# LoraEp.net
KiCad netlist of a schematic drawn in Altium Designer
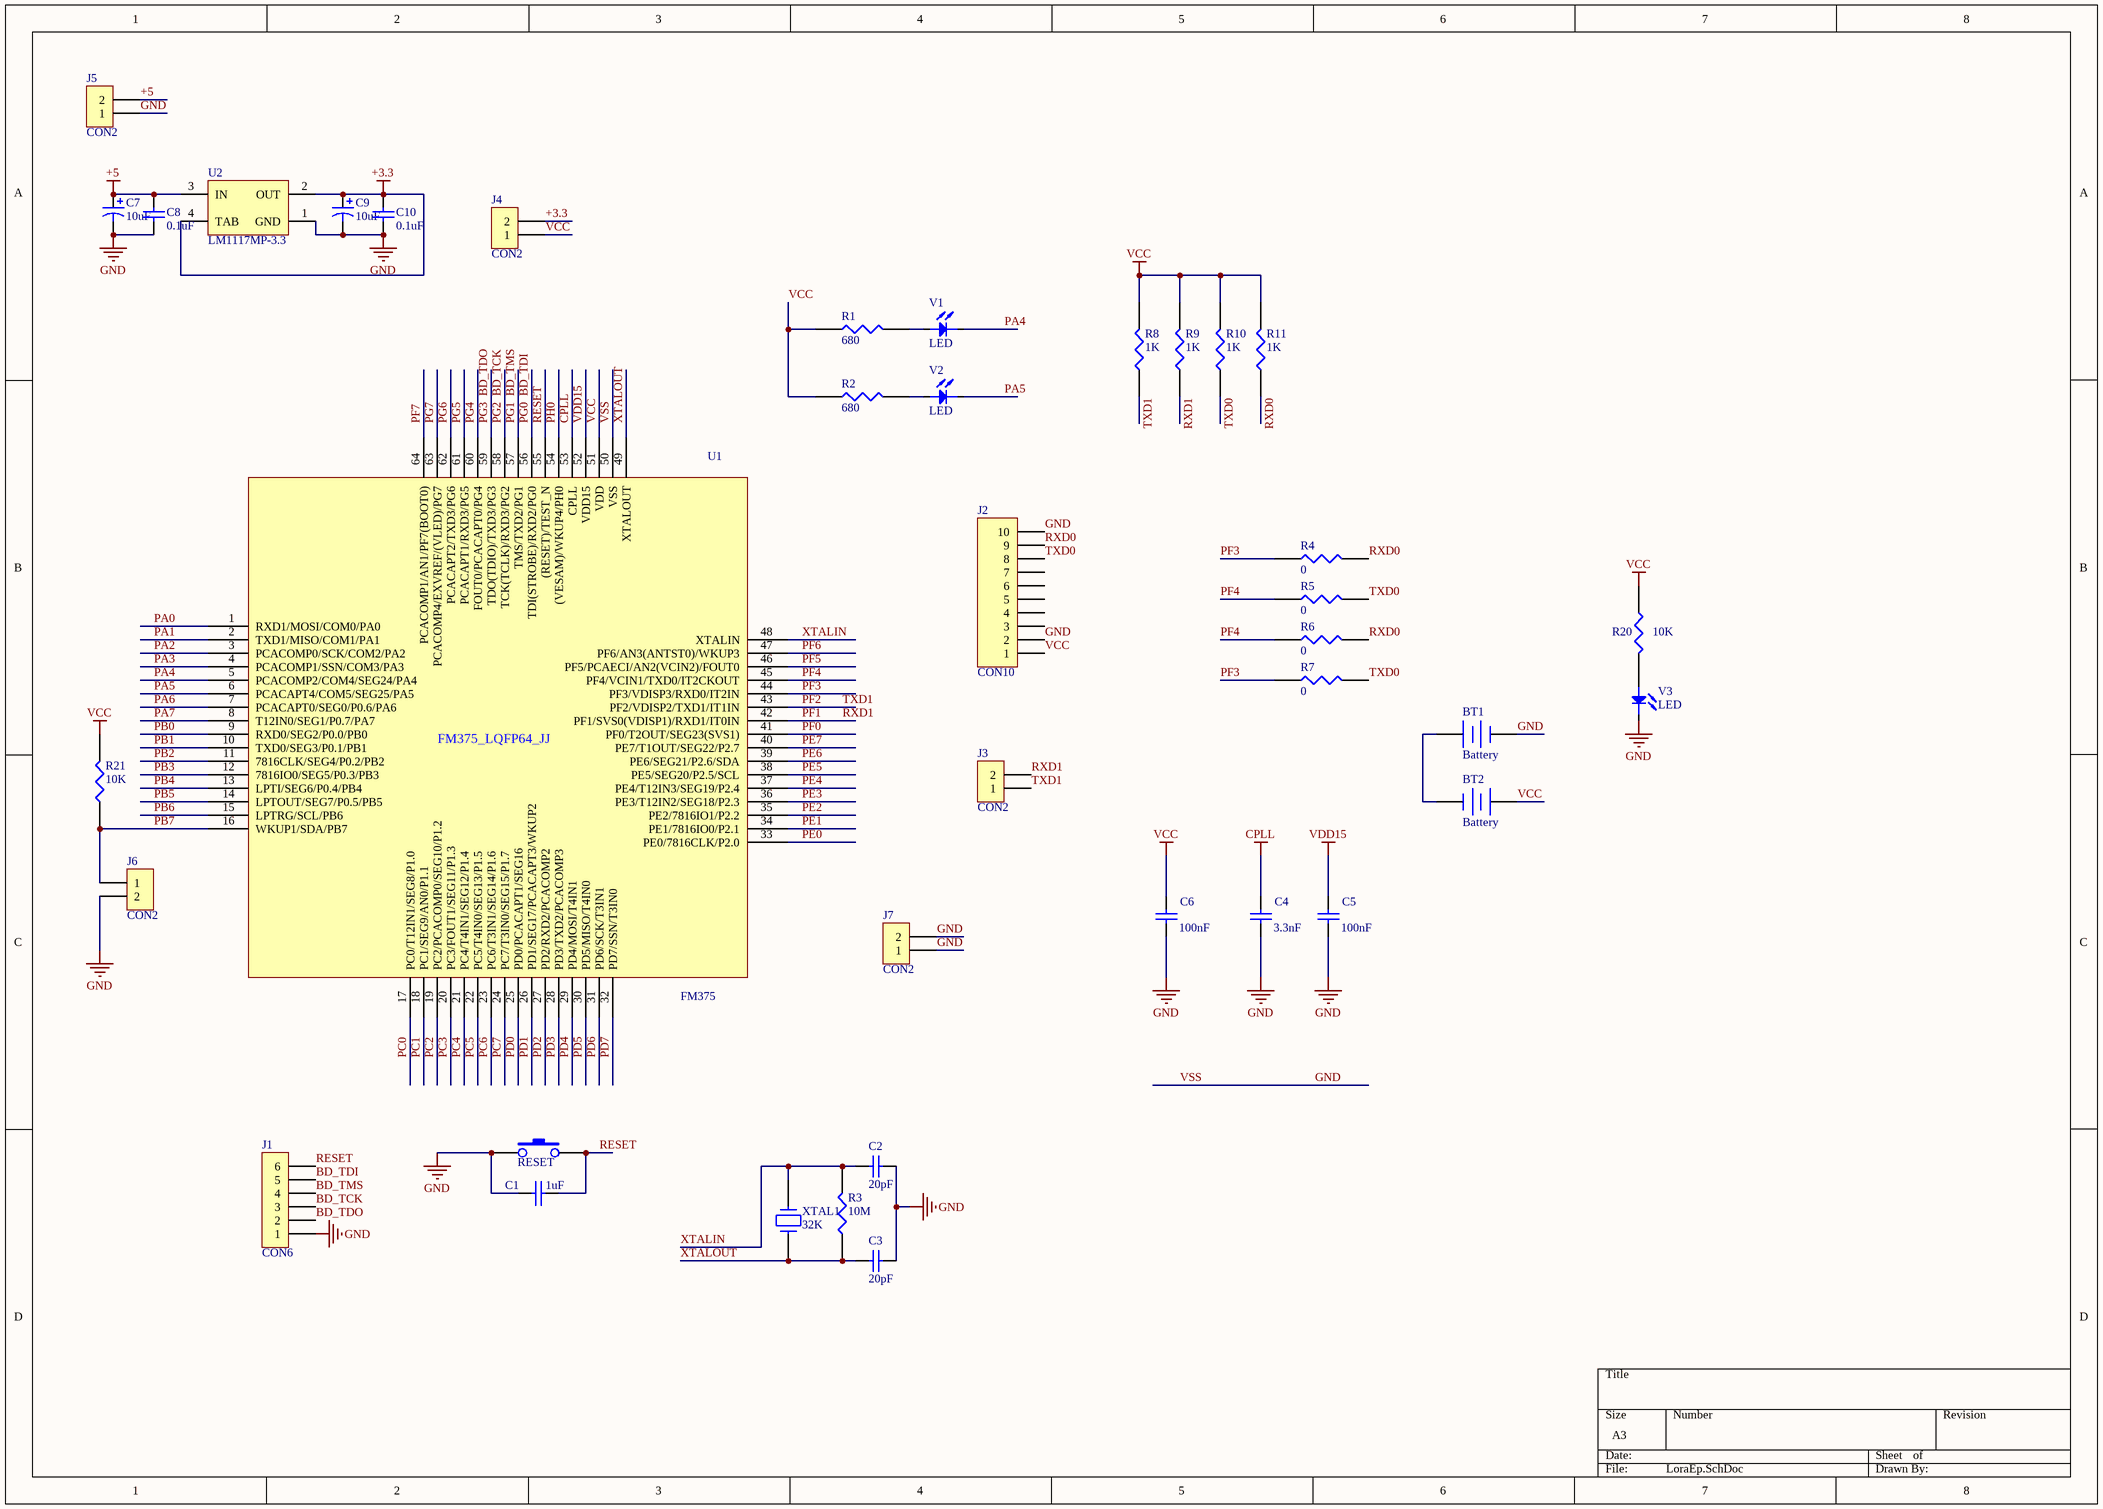
[diagram p0: LoraEp.SchDoc]

(export (version "E")
  (design (tool "Eeschema 10.0.6"))
  (components
    (comp (ref "BT1")
      (value "Battery")
      (footprint "BAT")
      (description "Multicell Battery")
      (fields (field (name "PUBLISHER") "Altium Limited"))
      (libsource (lib "Miscellaneous Devices") (part "Battery"))
    )
    (comp (ref "BT2")
      (value "Battery")
      (footprint "BAT")
      (description "Multicell Battery")
      (fields (field (name "PUBLISHER") "Altium Limited"))
      (libsource (lib "Miscellaneous Devices") (part "Battery"))
    )
    (comp (ref "C1")
      (value "1uF")
      (footprint "0805")
      (description "一般瓷片电容、直插选用RAD0.1，贴片选用0805")
      (libsource (lib "FM_SCH") (part "CAP"))
    )
    (comp (ref "C2")
      (value "20pF")
      (footprint "0805")
      (description "Capacitor")
      (fields (field (name "PUBLISHER") "Altium Limited"))
      (libsource (lib "Miscellaneous Devices") (part "Cap"))
    )
    (comp (ref "C3")
      (value "20pF")
      (footprint "0805")
      (description "Capacitor")
      (fields (field (name "PUBLISHER") "Altium Limited"))
      (libsource (lib "Miscellaneous Devices") (part "Cap"))
    )
    (comp (ref "C4")
      (value "3.3nF")
      (footprint "0805")
      (description "Capacitor")
      (fields (field (name "PUBLISHER") "Altium Limited"))
      (libsource (lib "Miscellaneous Devices") (part "Cap"))
    )
    (comp (ref "C5")
      (value "100nF")
      (footprint "0805")
      (description "Capacitor")
      (fields (field (name "PUBLISHER") "Altium Limited"))
      (libsource (lib "Miscellaneous Devices") (part "Cap"))
    )
    (comp (ref "C6")
      (value "100nF")
      (footprint "0805")
      (description "Capacitor")
      (fields (field (name "PUBLISHER") "Altium Limited"))
      (libsource (lib "Miscellaneous Devices") (part "Cap"))
    )
    (comp (ref "C7")
      (value "10uF")
      (footprint "0805")
      (description "Polarized Capacitor (Radial)")
      (fields (field (name "PUBLISHER") "Altium Limited"))
      (libsource (lib "Miscellaneous Devices") (part "Cap Pol1"))
    )
    (comp (ref "C8")
      (value "0.1uF")
      (footprint "0805")
      (description "Capacitor")
      (fields (field (name "PUBLISHER") "Altium Limited"))
      (libsource (lib "Miscellaneous Devices") (part "Cap"))
    )
    (comp (ref "C9")
      (value "10uF")
      (footprint "0805")
      (description "Polarized Capacitor (Radial)")
      (fields (field (name "PUBLISHER") "Altium Limited"))
      (libsource (lib "Miscellaneous Devices") (part "Cap Pol1"))
    )
    (comp (ref "C10")
      (value "0.1uF")
      (footprint "0805")
      (description "Capacitor")
      (fields (field (name "PUBLISHER") "Altium Limited"))
      (libsource (lib "Miscellaneous Devices") (part "Cap"))
    )
    (comp (ref "J1")
      (value "CON6")
      (footprint "SIP6")
      (description "Connector")
      (libsource (lib "YPF") (part "CON6"))
    )
    (comp (ref "J2")
      (value "CON10")
      (footprint "SSIP10")
      (description "Connector")
      (libsource (lib "YPF") (part "CON10"))
    )
    (comp (ref "J3")
      (value "CON2")
      (footprint "SIP2")
      (description "Connector")
      (libsource (lib "YPF") (part "CON2"))
    )
    (comp (ref "J4")
      (value "CON2")
      (footprint "SIP2")
      (description "Connector")
      (libsource (lib "YPF") (part "CON2"))
    )
    (comp (ref "J5")
      (value "CON2")
      (footprint "SourPad")
      (description "Connector")
      (libsource (lib "YPF") (part "CON2"))
    )
    (comp (ref "J6")
      (value "CON2")
      (footprint "SIP2")
      (description "Connector")
      (libsource (lib "") (part "CON2_1"))
    )
    (comp (ref "J7")
      (value "CON2")
      (footprint "HDR1X2")
      (description "Connector")
      (libsource (lib "YPF") (part "CON2"))
    )
    (comp (ref "R1")
      (value "680")
      (footprint "0805")
      (description "电阻，1/4w的金属膜直插可选AXIAL0.4封装（长度10mm），贴片可选0805封装，其他电阻可选AXIAL0.5～AXIAL1.0")
      (libsource (lib "*") (part "RES1"))
    )
    (comp (ref "R2")
      (value "680")
      (footprint "0805")
      (description "电阻，1/4w的金属膜直插可选AXIAL0.4封装（长度10mm），贴片可选0805封装，其他电阻可选AXIAL0.5～AXIAL1.0")
      (libsource (lib "*") (part "RES1"))
    )
    (comp (ref "R3") (value "10M") (footprint "0805") (libsource (lib "FM301_TEST") (part "RES1")))
    (comp (ref "R4")
      (value "0")
      (footprint "0805")
      (description "电阻，1/4w的金属膜直插可选AXIAL0.4封装（长度10mm），贴片可选0805封装，其他电阻可选AXIAL0.5～AXIAL1.0")
      (libsource (lib "*") (part "RES1"))
    )
    (comp (ref "R5")
      (value "0")
      (footprint "0805")
      (description "电阻，1/4w的金属膜直插可选AXIAL0.4封装（长度10mm），贴片可选0805封装，其他电阻可选AXIAL0.5～AXIAL1.0")
      (libsource (lib "*") (part "RES1"))
    )
    (comp (ref "R6")
      (value "0")
      (footprint "0805")
      (description "电阻，1/4w的金属膜直插可选AXIAL0.4封装（长度10mm），贴片可选0805封装，其他电阻可选AXIAL0.5～AXIAL1.0")
      (libsource (lib "*") (part "RES1"))
    )
    (comp (ref "R7")
      (value "0")
      (footprint "0805")
      (description "电阻，1/4w的金属膜直插可选AXIAL0.4封装（长度10mm），贴片可选0805封装，其他电阻可选AXIAL0.5～AXIAL1.0")
      (libsource (lib "*") (part "RES1"))
    )
    (comp (ref "R8")
      (value "1K")
      (footprint "0805")
      (description "电阻，1/4w的金属膜直插可选AXIAL0.4封装（长度10mm），贴片可选0805封装，其他电阻可选AXIAL0.5～AXIAL1.0")
      (libsource (lib "*") (part "RES1"))
    )
    (comp (ref "R9")
      (value "1K")
      (footprint "0805")
      (description "电阻，1/4w的金属膜直插可选AXIAL0.4封装（长度10mm），贴片可选0805封装，其他电阻可选AXIAL0.5～AXIAL1.0")
      (libsource (lib "*") (part "RES1"))
    )
    (comp (ref "R10")
      (value "1K")
      (footprint "0805")
      (description "电阻，1/4w的金属膜直插可选AXIAL0.4封装（长度10mm），贴片可选0805封装，其他电阻可选AXIAL0.5～AXIAL1.0")
      (libsource (lib "*") (part "RES1"))
    )
    (comp (ref "R11")
      (value "1K")
      (footprint "0805")
      (description "电阻，1/4w的金属膜直插可选AXIAL0.4封装（长度10mm），贴片可选0805封装，其他电阻可选AXIAL0.5～AXIAL1.0")
      (libsource (lib "*") (part "RES1"))
    )
    (comp (ref "R20")
      (value "10K")
      (footprint "0805")
      (description "电阻，1/4w的金属膜直插可选AXIAL0.4封装（长度10mm），贴片可选0805封装，其他电阻可选AXIAL0.5～AXIAL1.0")
      (libsource (lib "*") (part "RES1"))
    )
    (comp (ref "R21")
      (value "10K")
      (footprint "0805")
      (description "电阻，1/4w的金属膜直插可选AXIAL0.4封装（长度10mm），贴片可选0805封装，其他电阻可选AXIAL0.5～AXIAL1.0")
      (libsource (lib "*") (part "RES1"))
    )
    (comp (ref "RESET")
      (value "KEY")
      (footprint "YPF:BUTTON-S")
      (description "乒乓球按键（压下后接通，松开自动断开），较大按键尺寸12mmX12mm选用BUTTON-L封装，较小尺寸6mmX6mm选用BUTTON-S封装")
      (libsource (lib "*") (part "SW-PB"))
    )
    (comp (ref "U1")
      (value "FM375")
      (footprint "LQFP64-0.5")
      (libsource (lib "FM375_LQFP64_SOCKET") (part "LQFP64-JJ"))
    )
    (comp (ref "U2")
      (value "LM1117MP-3.3")
      (footprint "MP04A_L")
      (description "800mA Low-Dropout Linear Regulator")
      (fields
        (field (name "MANUFACTURER") "National Semiconductor")
        (field (name "DIGIKEYPARTNUMBER") "LM1117MP-3.3CT-ND")
        (field (name "PUBLISHER") "Altium Limited")
      )
      (libsource (lib "NSC LDO") (part "LM1117MP-3.3"))
    )
    (comp (ref "V1") (value "LED") (footprint "SIP2") (libsource (lib "YPF") (part "LED")))
    (comp (ref "V2") (value "LED") (footprint "SIP2") (libsource (lib "YPF") (part "LED")))
    (comp (ref "V3") (value "LED") (footprint "0805") (libsource (lib "YPF") (part "LED")))
    (comp (ref "XTAL1")
      (value "32K")
      (footprint "XTAL-RB32K_2")
      (description "Crystal")
      (libsource (lib "FM301_TEST") (part "CRYSTAL"))
    )
  )
  (nets
    (net (code "1") (name "+3.3") (class "Default")
      (node (ref "C10") (pin "2") (pinfunction "2_2") (pintype "passive"))
      (node (ref "C9") (pin "1") (pinfunction "1_1") (pintype "passive"))
      (node (ref "J4") (pin "2") (pinfunction "2_2") (pintype "passive"))
      (node (ref "U2") (pin "2") (pinfunction "OUT_2") (pintype "power_in"))
      (node (ref "U2") (pin "4") (pinfunction "TAB_4") (pintype "power_in"))
    )
    (net (code "2") (name "+5") (class "Default")
      (node (ref "C7") (pin "1") (pinfunction "1_1") (pintype "passive"))
      (node (ref "C8") (pin "2") (pinfunction "2_2") (pintype "passive"))
      (node (ref "J5") (pin "2") (pinfunction "2_2") (pintype "passive"))
      (node (ref "U2") (pin "3") (pinfunction "IN_3") (pintype "power_in"))
    )
    (net (code "3") (name "/BD_TCK") (class "Default")
      (node (ref "J1") (pin "3") (pinfunction "3_3") (pintype "passive"))
      (node (ref "U1") (pin "58") (pinfunction "TCK(TCLK)/RXD3/PG2_58") (pintype "passive"))
    )
    (net (code "4") (name "/BD_TDI") (class "Default")
      (node (ref "J1") (pin "5") (pinfunction "5_5") (pintype "passive"))
      (node (ref "U1") (pin "56") (pinfunction "TDI(STROBE)/RXD2/PG0_56") (pintype "passive"))
    )
    (net (code "5") (name "/BD_TDO") (class "Default")
      (node (ref "J1") (pin "2") (pinfunction "2_2") (pintype "passive"))
      (node (ref "U1") (pin "59") (pinfunction "TDO(TDIO)/TXD3/PG3_59") (pintype "passive"))
    )
    (net (code "6") (name "/BD_TMS") (class "Default")
      (node (ref "J1") (pin "4") (pinfunction "4_4") (pintype "passive"))
      (node (ref "U1") (pin "57") (pinfunction "TMS/TXD2/PG1_57") (pintype "passive"))
    )
    (net (code "7") (name "/PA0") (class "Default")
      (node (ref "U1") (pin "1") (pinfunction "RXD1/MOSI/COM0/PA0_1") (pintype "passive"))
    )
    (net (code "8") (name "/PA1") (class "Default")
      (node (ref "U1") (pin "2") (pinfunction "TXD1/MISO/COM1/PA1_2") (pintype "passive"))
    )
    (net (code "9") (name "/PA2") (class "Default")
      (node (ref "U1") (pin "3") (pinfunction "PCACOMP0/SCK/COM2/PA2_3") (pintype "passive"))
    )
    (net (code "10") (name "/PA3") (class "Default")
      (node (ref "U1") (pin "4") (pinfunction "PCACOMP1/SSN/COM3/PA3_4") (pintype "passive"))
    )
    (net (code "11") (name "/PA4") (class "Default")
      (node (ref "U1") (pin "5") (pinfunction "PCACOMP2/COM4/SEG24/PA4_5") (pintype "passive"))
      (node (ref "V1") (pin "2") (pintype "passive"))
    )
    (net (code "12") (name "/PA5") (class "Default")
      (node (ref "U1") (pin "6") (pinfunction "PCACAPT4/COM5/SEG25/PA5_6") (pintype "passive"))
      (node (ref "V2") (pin "2") (pintype "passive"))
    )
    (net (code "13") (name "/PA6") (class "Default")
      (node (ref "U1") (pin "7") (pinfunction "PCACAPT0/SEG0/P0.6/PA6_7") (pintype "passive"))
    )
    (net (code "14") (name "/PA7") (class "Default")
      (node (ref "U1") (pin "8") (pinfunction "T12IN0/SEG1/P0.7/PA7_8") (pintype "passive"))
    )
    (net (code "15") (name "/PB0") (class "Default")
      (node (ref "U1") (pin "9") (pinfunction "RXD0/SEG2/P0.0/PB0_9") (pintype "passive"))
    )
    (net (code "16") (name "/PB1") (class "Default")
      (node (ref "U1") (pin "10") (pinfunction "TXD0/SEG3/P0.1/PB1_10") (pintype "passive"))
    )
    (net (code "17") (name "/PB2") (class "Default")
      (node (ref "U1") (pin "11") (pinfunction "7816CLK/SEG4/P0.2/PB2_11") (pintype "passive"))
    )
    (net (code "18") (name "/PB3") (class "Default")
      (node (ref "U1") (pin "12") (pinfunction "7816IO0/SEG5/P0.3/PB3_12") (pintype "passive"))
    )
    (net (code "19") (name "/PB4") (class "Default")
      (node (ref "U1") (pin "13") (pinfunction "LPTI/SEG6/P0.4/PB4_13") (pintype "passive"))
    )
    (net (code "20") (name "/PB5") (class "Default")
      (node (ref "U1") (pin "14") (pinfunction "LPTOUT/SEG7/P0.5/PB5_14") (pintype "passive"))
    )
    (net (code "21") (name "/PB6") (class "Default")
      (node (ref "U1") (pin "15") (pinfunction "LPTRG/SCL/PB6_15") (pintype "passive"))
    )
    (net (code "22") (name "/PB7") (class "Default")
      (node (ref "J6") (pin "1") (pinfunction "1_1") (pintype "passive"))
      (node (ref "R21") (pin "1") (pinfunction "1_1") (pintype "passive"))
      (node (ref "U1") (pin "16") (pinfunction "WKUP1/SDA/PB7_16") (pintype "passive"))
    )
    (net (code "23") (name "/PC0") (class "Default")
      (node (ref "U1") (pin "17") (pinfunction "PC0/T12IN1/SEG8/P1.0_17") (pintype "passive"))
    )
    (net (code "24") (name "/PC1") (class "Default")
      (node (ref "U1") (pin "18") (pinfunction "PC1/SEG9/AN0/P1.1_18") (pintype "passive"))
    )
    (net (code "25") (name "/PC2") (class "Default")
      (node (ref "U1") (pin "19") (pinfunction "PC2/PCACOMP0/SEG10/P1.2_19") (pintype "passive"))
    )
    (net (code "26") (name "/PC3") (class "Default")
      (node (ref "U1") (pin "20") (pinfunction "PC3/FOUT1/SEG11/P1.3_20") (pintype "passive"))
    )
    (net (code "27") (name "/PC4") (class "Default")
      (node (ref "U1") (pin "21") (pinfunction "PC4/T4IN1/SEG12/P1.4_21") (pintype "passive"))
    )
    (net (code "28") (name "/PC5") (class "Default")
      (node (ref "U1") (pin "22") (pinfunction "PC5/T4IN0/SEG13/P1.5_22") (pintype "passive"))
    )
    (net (code "29") (name "/PC6") (class "Default")
      (node (ref "U1") (pin "23") (pinfunction "PC6/T3IN1/SEG14/P1.6_23") (pintype "passive"))
    )
    (net (code "30") (name "/PC7") (class "Default")
      (node (ref "U1") (pin "24") (pinfunction "PC7/T3IN0/SEG15/P1.7_24") (pintype "passive"))
    )
    (net (code "31") (name "/PD0") (class "Default")
      (node (ref "U1") (pin "25") (pinfunction "PD0/PCACAPT1/SEG16_25") (pintype "passive"))
    )
    (net (code "32") (name "/PD1") (class "Default")
      (node (ref "U1") (pin "26") (pinfunction "PD1/SEG17/PCACAPT3/WKUP2_26") (pintype "passive"))
    )
    (net (code "33") (name "/PD2") (class "Default")
      (node (ref "U1") (pin "27") (pinfunction "PD2/RXD2/PCACOMP2_27") (pintype "passive"))
    )
    (net (code "34") (name "/PD3") (class "Default")
      (node (ref "U1") (pin "28") (pinfunction "PD3/TXD2/PCACOMP3_28") (pintype "passive"))
    )
    (net (code "35") (name "/PD4") (class "Default")
      (node (ref "U1") (pin "29") (pinfunction "PD4/MOSI/T4IN1_29") (pintype "passive"))
    )
    (net (code "36") (name "/PD5") (class "Default")
      (node (ref "U1") (pin "30") (pinfunction "PD5/MISO/T4IN0_30") (pintype "passive"))
    )
    (net (code "37") (name "/PD6") (class "Default")
      (node (ref "U1") (pin "31") (pinfunction "PD6/SCK/T3IN1_31") (pintype "passive"))
    )
    (net (code "38") (name "/PD7") (class "Default")
      (node (ref "U1") (pin "32") (pinfunction "PD7/SSN/T3IN0_32") (pintype "passive"))
    )
    (net (code "39") (name "/PE0") (class "Default")
      (node (ref "U1") (pin "33") (pinfunction "PE0/7816CLK/P2.0_33") (pintype "passive"))
    )
    (net (code "40") (name "/PE1") (class "Default")
      (node (ref "U1") (pin "34") (pinfunction "PE1/7816IO0/P2.1_34") (pintype "passive"))
    )
    (net (code "41") (name "/PE2") (class "Default")
      (node (ref "U1") (pin "35") (pinfunction "PE2/7816IO1/P2.2_35") (pintype "passive"))
    )
    (net (code "42") (name "/PE3") (class "Default")
      (node (ref "U1") (pin "36") (pinfunction "PE3/T12IN2/SEG18/P2.3_36") (pintype "passive"))
    )
    (net (code "43") (name "/PE4") (class "Default")
      (node (ref "U1") (pin "37") (pinfunction "PE4/T12IN3/SEG19/P2.4_37") (pintype "passive"))
    )
    (net (code "44") (name "/PE5") (class "Default")
      (node (ref "U1") (pin "38") (pinfunction "PE5/SEG20/P2.5/SCL_38") (pintype "passive"))
    )
    (net (code "45") (name "/PE6") (class "Default")
      (node (ref "U1") (pin "39") (pinfunction "PE6/SEG21/P2.6/SDA_39") (pintype "passive"))
    )
    (net (code "46") (name "/PE7") (class "Default")
      (node (ref "U1") (pin "40") (pinfunction "PE7/T1OUT/SEG22/P2.7_40") (pintype "passive"))
    )
    (net (code "47") (name "/PF0") (class "Default")
      (node (ref "U1") (pin "41") (pinfunction "PF0/T2OUT/SEG23(SVS1)_41") (pintype "passive"))
    )
    (net (code "48") (name "/PF1") (class "Default")
      (node (ref "J3") (pin "2") (pinfunction "2_2") (pintype "passive"))
      (node (ref "R9") (pin "1") (pinfunction "1_1") (pintype "passive"))
      (node (ref "U1") (pin "42") (pinfunction "PF1/SVS0(VDISP1)/RXD1/IT0IN_42") (pintype "passive"))
    )
    (net (code "49") (name "/PF2") (class "Default")
      (node (ref "J3") (pin "1") (pinfunction "1_1") (pintype "passive"))
      (node (ref "R8") (pin "1") (pinfunction "1_1") (pintype "passive"))
      (node (ref "U1") (pin "43") (pinfunction "PF2/VDISP2/TXD1/IT1IN_43") (pintype "passive"))
    )
    (net (code "50") (name "/PF3") (class "Default")
      (node (ref "R4") (pin "1") (pinfunction "1_1") (pintype "passive"))
      (node (ref "R7") (pin "1") (pinfunction "1_1") (pintype "passive"))
      (node (ref "U1") (pin "44") (pinfunction "PF3/VDISP3/RXD0/IT2IN_44") (pintype "passive"))
    )
    (net (code "51") (name "/PF4") (class "Default")
      (node (ref "R5") (pin "1") (pinfunction "1_1") (pintype "passive"))
      (node (ref "R6") (pin "1") (pinfunction "1_1") (pintype "passive"))
      (node (ref "U1") (pin "45") (pinfunction "PF4/VCIN1/TXD0/IT2CKOUT_45") (pintype "passive"))
    )
    (net (code "52") (name "/PF5") (class "Default")
      (node (ref "U1") (pin "46") (pinfunction "PF5/PCAECI/AN2(VCIN2)/FOUT0_46") (pintype "passive"))
    )
    (net (code "53") (name "/PF6") (class "Default")
      (node (ref "U1") (pin "47") (pinfunction "PF6/AN3(ANTST0)/WKUP3_47") (pintype "passive"))
    )
    (net (code "54") (name "/PF7") (class "Default")
      (node (ref "U1") (pin "64") (pinfunction "PCACOMP1/AN1/PF7(BOOT0)_64") (pintype "passive"))
    )
    (net (code "55") (name "/PG4") (class "Default")
      (node (ref "U1") (pin "60") (pinfunction "FOUT0/PCACAPT0/PG4_60") (pintype "passive"))
    )
    (net (code "56") (name "/PG5") (class "Default")
      (node (ref "U1") (pin "61") (pinfunction "PCACAPT1/RXD3/PG5_61") (pintype "passive"))
    )
    (net (code "57") (name "/PG6") (class "Default")
      (node (ref "U1") (pin "62") (pinfunction "PCACAPT2/TXD3/PG6_62") (pintype "passive"))
    )
    (net (code "58") (name "/PG7") (class "Default")
      (node (ref "U1") (pin "63") (pinfunction "PCACOMP4/EXVREF/(VLED)/PG7_63") (pintype "passive"))
    )
    (net (code "59") (name "/PH0") (class "Default")
      (node (ref "U1") (pin "54") (pinfunction "(VESAM)/WKUP4/PH0_54") (pintype "passive"))
    )
    (net (code "60") (name "/RESET") (class "Default")
      (node (ref "C1") (pin "1") (pinfunction "1_1") (pintype "passive"))
      (node (ref "J1") (pin "6") (pinfunction "6_6") (pintype "passive"))
      (node (ref "RESET") (pin "2") (pinfunction "2_2") (pintype "passive"))
      (node (ref "U1") (pin "55") (pinfunction "(RESET)/TEST_N_55") (pintype "passive"))
    )
    (net (code "61") (name "/RXD0") (class "Default")
      (node (ref "J2") (pin "9") (pinfunction "9_9") (pintype "passive"))
      (node (ref "R11") (pin "1") (pinfunction "1_1") (pintype "passive"))
      (node (ref "R4") (pin "2") (pinfunction "2_2") (pintype "passive"))
      (node (ref "R6") (pin "2") (pinfunction "2_2") (pintype "passive"))
    )
    (net (code "62") (name "/TXD0") (class "Default")
      (node (ref "J2") (pin "8") (pinfunction "8_8") (pintype "passive"))
      (node (ref "R10") (pin "1") (pinfunction "1_1") (pintype "passive"))
      (node (ref "R5") (pin "2") (pinfunction "2_2") (pintype "passive"))
      (node (ref "R7") (pin "2") (pinfunction "2_2") (pintype "passive"))
    )
    (net (code "63") (name "/XTALIN") (class "Default")
      (node (ref "C2") (pin "1") (pinfunction "1_1") (pintype "passive"))
      (node (ref "R3") (pin "2") (pinfunction "2_2") (pintype "passive"))
      (node (ref "U1") (pin "48") (pinfunction "XTALIN_48") (pintype "passive"))
      (node (ref "XTAL1") (pin "2") (pinfunction "2_2") (pintype "passive"))
    )
    (net (code "64") (name "/XTALOUT") (class "Default")
      (node (ref "C3") (pin "1") (pinfunction "1_1") (pintype "passive"))
      (node (ref "R3") (pin "1") (pinfunction "1_1") (pintype "passive"))
      (node (ref "U1") (pin "49") (pinfunction "XTALOUT_49") (pintype "passive"))
      (node (ref "XTAL1") (pin "1") (pinfunction "1_1") (pintype "passive"))
    )
    (net (code "65") (name "CPLL") (class "Default")
      (node (ref "C4") (pin "2") (pinfunction "2_2") (pintype "passive"))
      (node (ref "U1") (pin "53") (pinfunction "CPLL_53") (pintype "passive"))
    )
    (net (code "66") (name "GND") (class "Default")
      (node (ref "BT1") (pin "2") (pinfunction "-_2") (pintype "passive"))
      (node (ref "C1") (pin "2") (pinfunction "2_2") (pintype "passive"))
      (node (ref "C10") (pin "1") (pinfunction "1_1") (pintype "passive"))
      (node (ref "C2") (pin "2") (pinfunction "2_2") (pintype "passive"))
      (node (ref "C3") (pin "2") (pinfunction "2_2") (pintype "passive"))
      (node (ref "C4") (pin "1") (pinfunction "1_1") (pintype "passive"))
      (node (ref "C5") (pin "1") (pinfunction "1_1") (pintype "passive"))
      (node (ref "C6") (pin "1") (pinfunction "1_1") (pintype "passive"))
      (node (ref "C7") (pin "2") (pinfunction "2_2") (pintype "passive"))
      (node (ref "C8") (pin "1") (pinfunction "1_1") (pintype "passive"))
      (node (ref "C9") (pin "2") (pinfunction "2_2") (pintype "passive"))
      (node (ref "J1") (pin "1") (pinfunction "1_1") (pintype "passive"))
      (node (ref "J2") (pin "10") (pinfunction "10_10") (pintype "passive"))
      (node (ref "J2") (pin "2") (pinfunction "2_2") (pintype "passive"))
      (node (ref "J5") (pin "1") (pinfunction "1_1") (pintype "passive"))
      (node (ref "J6") (pin "2") (pinfunction "2_2") (pintype "passive"))
      (node (ref "J7") (pin "1") (pinfunction "1_1") (pintype "passive"))
      (node (ref "J7") (pin "2") (pinfunction "2_2") (pintype "passive"))
      (node (ref "RESET") (pin "1") (pinfunction "1_1") (pintype "passive"))
      (node (ref "U1") (pin "50") (pinfunction "VSS_50") (pintype "passive"))
      (node (ref "U2") (pin "1") (pinfunction "GND_1") (pintype "power_in"))
      (node (ref "V3") (pin "2") (pintype "passive"))
    )
    (net (code "67") (name "Net-(BT1-+)") (class "Default")
      (node (ref "BT1") (pin "1") (pinfunction "+_1") (pintype "passive"))
      (node (ref "BT2") (pin "2") (pinfunction "-_2") (pintype "passive"))
    )
    (net (code "68") (name "Net-(R1-Pad2)") (class "Default")
      (node (ref "R1") (pin "2") (pinfunction "2_2") (pintype "passive"))
      (node (ref "V1") (pin "1") (pintype "passive"))
    )
    (net (code "69") (name "Net-(R2-Pad2)") (class "Default")
      (node (ref "R2") (pin "2") (pinfunction "2_2") (pintype "passive"))
      (node (ref "V2") (pin "1") (pintype "passive"))
    )
    (net (code "70") (name "Net-(R20-Pad2)") (class "Default")
      (node (ref "R20") (pin "2") (pinfunction "2_2") (pintype "passive"))
      (node (ref "V3") (pin "1") (pintype "passive"))
    )
    (net (code "71") (name "VCC") (class "Default")
      (node (ref "BT2") (pin "1") (pinfunction "+_1") (pintype "passive"))
      (node (ref "C6") (pin "2") (pinfunction "2_2") (pintype "passive"))
      (node (ref "J2") (pin "1") (pinfunction "1_1") (pintype "passive"))
      (node (ref "J4") (pin "1") (pinfunction "1_1") (pintype "passive"))
      (node (ref "R1") (pin "1") (pinfunction "1_1") (pintype "passive"))
      (node (ref "R10") (pin "2") (pinfunction "2_2") (pintype "passive"))
      (node (ref "R11") (pin "2") (pinfunction "2_2") (pintype "passive"))
      (node (ref "R2") (pin "1") (pinfunction "1_1") (pintype "passive"))
      (node (ref "R20") (pin "1") (pinfunction "1_1") (pintype "passive"))
      (node (ref "R21") (pin "2") (pinfunction "2_2") (pintype "passive"))
      (node (ref "R8") (pin "2") (pinfunction "2_2") (pintype "passive"))
      (node (ref "R9") (pin "2") (pinfunction "2_2") (pintype "passive"))
      (node (ref "U1") (pin "51") (pinfunction "VDD_51") (pintype "passive"))
    )
    (net (code "72") (name "VDD15") (class "Default")
      (node (ref "C5") (pin "2") (pinfunction "2_2") (pintype "passive"))
      (node (ref "U1") (pin "52") (pinfunction "VDD15_52") (pintype "passive"))
    )
    (net (code "73") (name "unconnected-(J2-Pad3)") (class "Default")
      (node (ref "J2") (pin "3") (pinfunction "3_3") (pintype "passive"))
    )
    (net (code "74") (name "unconnected-(J2-Pad4)") (class "Default")
      (node (ref "J2") (pin "4") (pinfunction "4_4") (pintype "passive"))
    )
    (net (code "75") (name "unconnected-(J2-Pad5)") (class "Default")
      (node (ref "J2") (pin "5") (pinfunction "5_5") (pintype "passive"))
    )
    (net (code "76") (name "unconnected-(J2-Pad6)") (class "Default")
      (node (ref "J2") (pin "6") (pinfunction "6_6") (pintype "passive"))
    )
    (net (code "77") (name "unconnected-(J2-Pad7)") (class "Default")
      (node (ref "J2") (pin "7") (pinfunction "7_7") (pintype "passive"))
    )
  )
)
